# Testing_Sockets.net
KiCad netlist of a schematic drawn in EAGLE
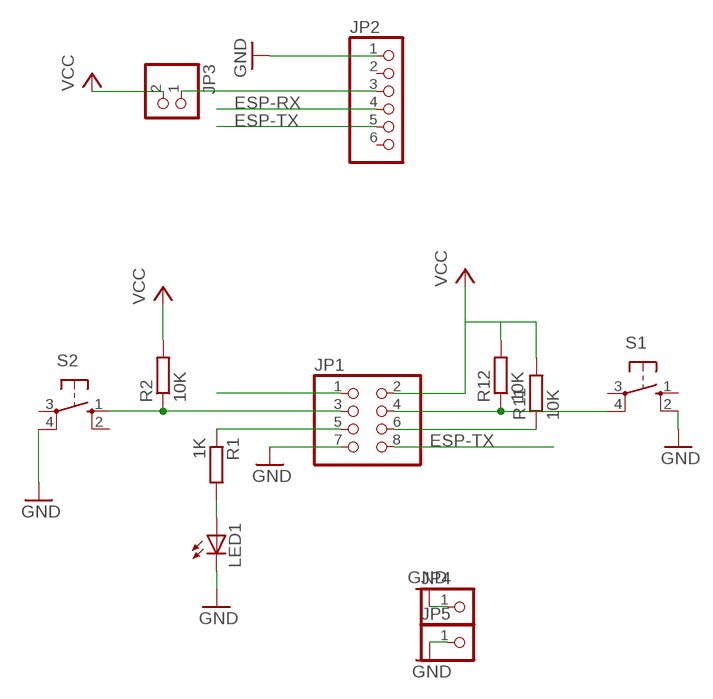
[diagram p0: schematic, sheet 1]

(export (version "E")
  (design (tool "Eeschema 10.0.6"))
  (components
    (comp (ref "JP1")
      (value "PINHD-2X4")
      (footprint "eagle-import:2X04")
      (libsource (lib "eagle-import") (part "PINHD-2X4"))
    )
    (comp (ref "JP2")
      (value "PINHD-1X6")
      (footprint "eagle-import:1X06")
      (libsource (lib "eagle-import") (part "PINHD-1X6"))
    )
    (comp (ref "JP3")
      (value "PINHD-1X2")
      (footprint "eagle-import:1X02")
      (libsource (lib "eagle-import") (part "PINHD-1X2"))
    )
    (comp (ref "JP4")
      (value "PINHD-1X1")
      (footprint "eagle-import:1X01")
      (libsource (lib "eagle-import") (part "PINHD-1X1"))
    )
    (comp (ref "JP5")
      (value "PINHD-1X1")
      (footprint "eagle-import:1X01")
      (libsource (lib "eagle-import") (part "PINHD-1X1"))
    )
    (comp (ref "LED1")
      (value "LED5MM")
      (footprint "eagle-import:LED5MM")
      (libsource (lib "eagle-import") (part "LED5MM"))
    )
    (comp (ref "R1")
      (value "1K")
      (footprint "eagle-import:0207_10")
      (libsource (lib "eagle-import") (part "R-EU_0207/10"))
    )
    (comp (ref "R2")
      (value "10K")
      (footprint "eagle-import:0207_10")
      (libsource (lib "eagle-import") (part "R-EU_0207/10"))
    )
    (comp (ref "R11")
      (value "10K")
      (footprint "eagle-import:0207_10")
      (libsource (lib "eagle-import") (part "R-EU_0207/10"))
    )
    (comp (ref "R12")
      (value "10K")
      (footprint "eagle-import:0207_10")
      (libsource (lib "eagle-import") (part "R-EU_0207/10"))
    )
    (comp (ref "S1")
      (value "10-XX")
      (footprint "eagle-import:B3F-10XX")
      (fields (field (name "MPN") "B3F-1000"))
      (libsource (lib "eagle-import") (part "10-XX"))
    )
    (comp (ref "S2")
      (value "10-XX")
      (footprint "eagle-import:B3F-10XX")
      (fields
        (field (name "MPN") "B3F-1000")
        (field (name "MPN_1") "B3F-1000")
        (field (name "OC_FARNELL") "176432")
        (field (name "OC_NEWARK") "36M3542")
      )
      (libsource (lib "eagle-import") (part "10-XX"))
    )
  )
  (nets
    (net (code "1") (name "/ESP-RX") (class "Default")
      (node (ref "JP1") (pin "1") (pinfunction "1_1") (pintype "passive"))
      (node (ref "JP2") (pin "4") (pinfunction "4_4") (pintype "passive"))
    )
    (net (code "2") (name "/ESP-TX") (class "Default")
      (node (ref "JP1") (pin "8") (pinfunction "8_8") (pintype "passive"))
      (node (ref "JP2") (pin "5") (pinfunction "5_5") (pintype "passive"))
    )
    (net (code "3") (name "GND") (class "Default")
      (node (ref "JP1") (pin "7") (pinfunction "7_7") (pintype "passive"))
      (node (ref "JP2") (pin "1") (pinfunction "1_1") (pintype "passive"))
      (node (ref "JP4") (pin "1") (pinfunction "1_1") (pintype "passive"))
      (node (ref "JP5") (pin "1") (pinfunction "1_1") (pintype "passive"))
      (node (ref "LED1") (pin "K") (pinfunction "C_K") (pintype "passive"))
      (node (ref "S1") (pin "2") (pinfunction "S1_2") (pintype "passive"))
      (node (ref "S2") (pin "4") (pinfunction "P1_4") (pintype "passive"))
    )
    (net (code "4") (name "Net-(JP1-Pad5)") (class "Default")
      (node (ref "JP1") (pin "5") (pinfunction "5_5") (pintype "passive"))
      (node (ref "R1") (pin "1") (pinfunction "1_1") (pintype "passive"))
    )
    (net (code "5") (name "Net-(JP1-Pad6)") (class "Default")
      (node (ref "JP1") (pin "6") (pinfunction "6_6") (pintype "passive"))
      (node (ref "R11") (pin "1") (pinfunction "1_1") (pintype "passive"))
    )
    (net (code "6") (name "Net-(JP2-Pad3)") (class "Default")
      (node (ref "JP2") (pin "3") (pinfunction "3_3") (pintype "passive"))
      (node (ref "JP3") (pin "1") (pinfunction "1_1") (pintype "passive"))
    )
    (net (code "7") (name "Net-(LED1-PadA)") (class "Default")
      (node (ref "LED1") (pin "A") (pinfunction "A_A") (pintype "passive"))
      (node (ref "R1") (pin "2") (pinfunction "2_2") (pintype "passive"))
    )
    (net (code "8") (name "Net-(S1-P1)") (class "Default")
      (node (ref "JP1") (pin "4") (pinfunction "4_4") (pintype "passive"))
      (node (ref "R12") (pin "1") (pinfunction "1_1") (pintype "passive"))
      (node (ref "S1") (pin "4") (pinfunction "P1_4") (pintype "passive"))
    )
    (net (code "9") (name "Net-(S2-S)") (class "Default")
      (node (ref "JP1") (pin "3") (pinfunction "3_3") (pintype "passive"))
      (node (ref "R2") (pin "1") (pinfunction "1_1") (pintype "passive"))
      (node (ref "S2") (pin "1") (pinfunction "S_1") (pintype "passive"))
    )
    (net (code "10") (name "VCC") (class "Default")
      (node (ref "JP1") (pin "2") (pinfunction "2_2") (pintype "passive"))
      (node (ref "JP3") (pin "2") (pinfunction "2_2") (pintype "passive"))
      (node (ref "R11") (pin "2") (pinfunction "2_2") (pintype "passive"))
      (node (ref "R12") (pin "2") (pinfunction "2_2") (pintype "passive"))
      (node (ref "R2") (pin "2") (pinfunction "2_2") (pintype "passive"))
    )
    (net (code "11") (name "unconnected-(JP2-Pad2)") (class "Default")
      (node (ref "JP2") (pin "2") (pinfunction "2_2") (pintype "passive"))
    )
    (net (code "12") (name "unconnected-(JP2-Pad6)") (class "Default")
      (node (ref "JP2") (pin "6") (pinfunction "6_6") (pintype "passive"))
    )
    (net (code "13") (name "unconnected-(S1-P-Pad3)") (class "Default")
      (node (ref "S1") (pin "3") (pinfunction "P_3") (pintype "passive"))
    )
    (net (code "14") (name "unconnected-(S1-S-Pad1)") (class "Default")
      (node (ref "S1") (pin "1") (pinfunction "S_1") (pintype "passive"))
    )
    (net (code "15") (name "unconnected-(S2-P-Pad3)") (class "Default")
      (node (ref "S2") (pin "3") (pinfunction "P_3") (pintype "passive"))
    )
    (net (code "16") (name "unconnected-(S2-S1-Pad2)") (class "Default")
      (node (ref "S2") (pin "2") (pinfunction "S1_2") (pintype "passive"))
    )
  )
)
